# LEM.net
KiCad netlist of a schematic drawn in Altium Designer
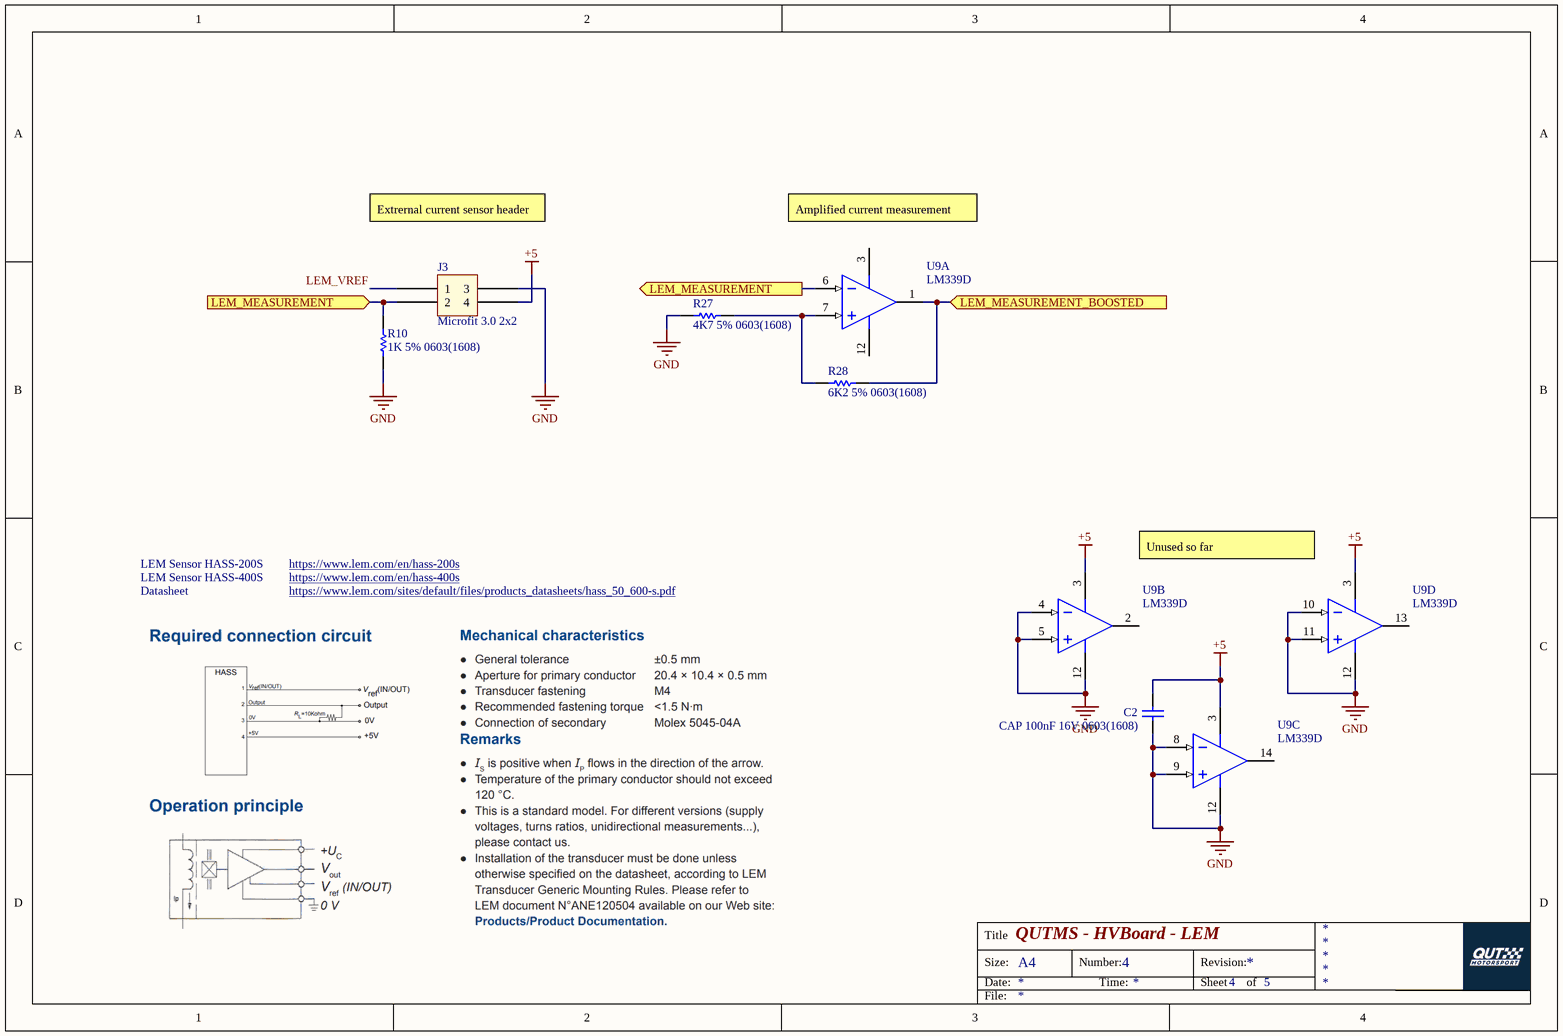
[diagram p0: LEM.SchDoc]

(export (version "E")
  (design (tool "Eeschema 10.0.6"))
  (components
    (comp (ref "C2")
      (value "CAP 100nF 16V 0603(1608)")
      (footprint "CAPC0603(1608)100_N")
      (description "CAP 100nF 16V ±10% 0603 (1608 Metric) Thickness 1mm SMD")
      (fields (field (name "TOLERANCE") "Â±10%"))
      (libsource (lib "Altium Content Vault") (part "CAP"))
    )
    (comp (ref "J3")
      (value "Microfit 3.0 2x2")
      (footprint "Microfit_2X2_R_TH")
      (libsource (lib "QUTMS_Microfit") (part "Microfit_2x2"))
    )
    (comp (ref "R10")
      (value "1K 5% 0603(1608)")
      (footprint "RESC0603(1608)_L")
      (description "1K 0.1W 5% 0603 (1608 Metric)  SMD")
      (fields (field (name "TOLERANCE") "5 %") (field (name "POWER") "0.1 W"))
      (libsource (lib "Altium Content Vault") (part "RES"))
    )
    (comp (ref "R27")
      (value "4K7 5% 0603(1608)")
      (footprint "RESC0603(1608)_N")
      (description "4K7 0.1W 5% 0603 (1608 Metric)  SMD")
      (fields (field (name "TOLERANCE") "5 %") (field (name "POWER") "0.1 W"))
      (libsource (lib "Altium Content Vault") (part "RES"))
    )
    (comp (ref "R28")
      (value "6K2 5% 0603(1608)")
      (footprint "RESC0603(1608)_L")
      (description "6K2 0.1W 5% 0603 (1608 Metric)  SMD")
      (fields (field (name "TOLERANCE") "5 %") (field (name "POWER") "0.1 W"))
      (libsource (lib "Altium Content Vault") (part "RES"))
    )
    (comp (ref "U9")
      (value "LM339D")
      (footprint "D0014A_L")
      (fields (field (name "MANUFACTURER") "Texas Instruments"))
      (libsource (lib "Altium Content Vault") (part "TI-LMXXXX14"))
    )
  )
  (nets
    (net (code "1") (name "+5") (class "Default")
      (node (ref "C2") (pin "2") (pinfunction "2_2") (pintype "passive"))
      (node (ref "J3") (pin "4") (pinfunction "4_4") (pintype "passive"))
      (node (ref "U9") (pin "3") (pinfunction "VCC_3") (pintype "power_in"))
    )
    (net (code "2") (name "/LEM_MEASUREMENT") (class "Default")
      (node (ref "J3") (pin "2") (pinfunction "2_2") (pintype "passive"))
      (node (ref "R10") (pin "2") (pinfunction "2_2") (pintype "passive"))
      (node (ref "U9") (pin "6") (pinfunction "IN1-_6") (pintype "input"))
    )
    (net (code "3") (name "/LEM_MEASUREMENT_BOOSTED") (class "Default")
      (node (ref "R28") (pin "2") (pinfunction "2_2") (pintype "passive"))
      (node (ref "U9") (pin "1") (pinfunction "OUT1_1") (pintype "open_collector"))
    )
    (net (code "4") (name "/LEM_VREF") (class "Default")
      (node (ref "J3") (pin "1") (pinfunction "1_1") (pintype "passive"))
    )
    (net (code "5") (name "GND") (class "Default")
      (node (ref "C2") (pin "1") (pinfunction "1_1") (pintype "passive"))
      (node (ref "J3") (pin "3") (pinfunction "3_3") (pintype "passive"))
      (node (ref "R10") (pin "1") (pinfunction "1_1") (pintype "passive"))
      (node (ref "R27") (pin "2") (pinfunction "2_2") (pintype "passive"))
      (node (ref "U9") (pin "10") (pinfunction "IN4-_10") (pintype "input"))
      (node (ref "U9") (pin "11") (pinfunction "IN4+_11") (pintype "input"))
      (node (ref "U9") (pin "12") (pinfunction "GND_12") (pintype "power_in"))
      (node (ref "U9") (pin "4") (pinfunction "IN2-_4") (pintype "input"))
      (node (ref "U9") (pin "5") (pinfunction "IN2+_5") (pintype "input"))
      (node (ref "U9") (pin "8") (pinfunction "IN3-_8") (pintype "input"))
      (node (ref "U9") (pin "9") (pinfunction "IN3+_9") (pintype "input"))
    )
    (net (code "6") (name "Net-(U9A-IN1+)") (class "Default")
      (node (ref "R27") (pin "1") (pinfunction "1_1") (pintype "passive"))
      (node (ref "R28") (pin "1") (pinfunction "1_1") (pintype "passive"))
      (node (ref "U9") (pin "7") (pinfunction "IN1+_7") (pintype "input"))
    )
    (net (code "7") (name "unconnected-(U9A-GND-Pad12)") (class "Default")
      (node (ref "U9") (pin "12") (pinfunction "GND_12") (pintype "power_in"))
    )
    (net (code "8") (name "unconnected-(U9A-VCC-Pad3)") (class "Default")
      (node (ref "U9") (pin "3") (pinfunction "VCC_3") (pintype "power_in"))
    )
    (net (code "9") (name "unconnected-(U9B-OUT2-Pad2)") (class "Default")
      (node (ref "U9") (pin "2") (pinfunction "OUT2_2") (pintype "open_collector"))
    )
    (net (code "10") (name "unconnected-(U9C-OUT3-Pad14)") (class "Default")
      (node (ref "U9") (pin "14") (pinfunction "OUT3_14") (pintype "open_collector"))
    )
    (net (code "11") (name "unconnected-(U9D-OUT4-Pad13)") (class "Default")
      (node (ref "U9") (pin "13") (pinfunction "OUT4_13") (pintype "open_collector"))
    )
  )
)
